# Power_Circuit.net
KiCad netlist of a schematic drawn in Altium Designer
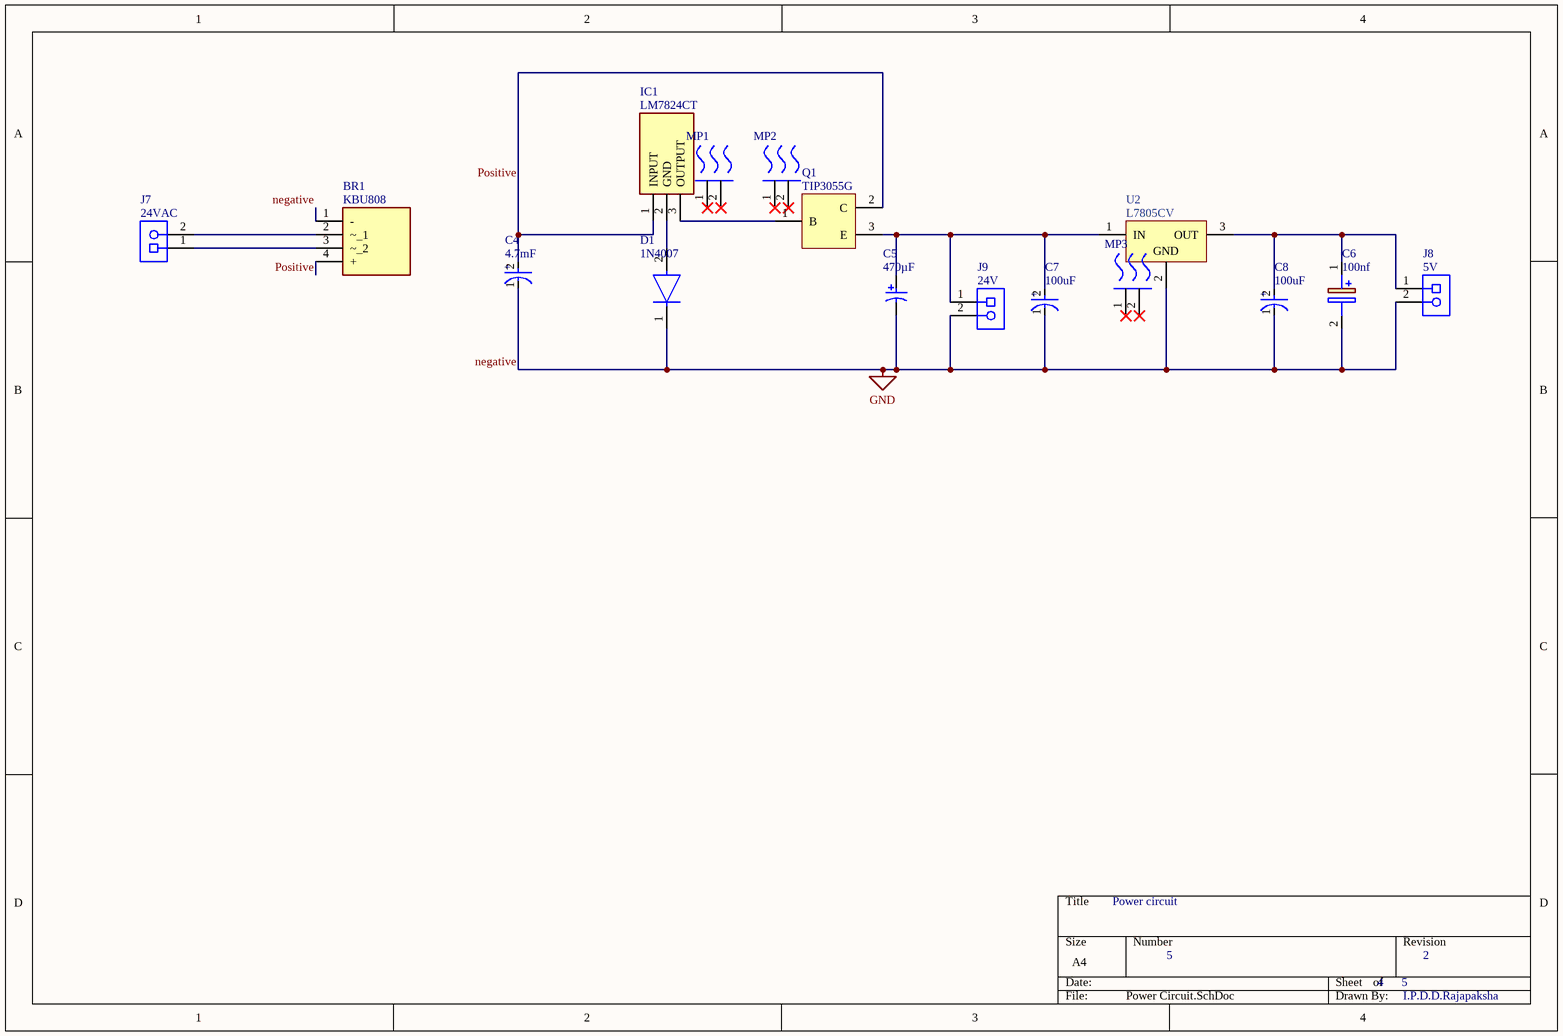
[diagram p0: Power Circuit.SchDoc]

(export (version "E")
  (design (tool "Eeschema 10.0.6"))
  (components
    (comp (ref "BR1")
      (value "KBU808")
      (footprint "SamacSys:KBU808")
      (description "Bridge Rectifier")
      (libsource (lib "SamacSys") (part "KBU808"))
    )
    (comp (ref "C4")
      (value "ECA1VHG472")
      (footprint "FP-RAD-TH-D_18_0_5-L_35_5-MFG")
      (description "Aluminum Electrolytic Capacitors (Radial Lead Type) AEC-Q200 Qualified 4700uF ±20% 35V")
      (fields
        (field (name "CAPACITANCE") "4.7mF")
        (field (name "VOLTAGE") "35V")
        (field (name "TOLERANCE") "20%")
      )
      (libsource (lib "Altium Content Vault") (part "203bc49f2ac43e59fd269a8c329ed05"))
    )
    (comp (ref "C5")
      (value "ECA-1HHG471")
      (footprint "PNSC-CAP-10x20-P2")
      (description "Aluminum Electrolytic Capacitor, 470 uF, +/- 20%, 50 V, -55 to 105 degC, 2-Pin THD, RoHS, Bulk")
      (fields (field (name "MANUFACTURER") "Panasonic") (field (name "CAPACITANCE") "470µF"))
      (libsource (lib "Altium Content Vault") (part "CAP-P-2"))
    )
    (comp (ref "C6")
      (value "ECEA1HKS0R1")
      (footprint "SamacSys:CAPPRD150W50D400H600")
      (description "Capacitor Polarised")
      (fields (field (name "PARAMETER 1") "100nf"))
      (libsource (lib "*") (part "ECEA1HKS0R1"))
    )
    (comp (ref "C7")
      (value "EEU-FR1H101B")
      (footprint "FP-EEU-FR1H101B-MFG")
      (description "CAP ALUM 100UF 20% 50V RADIAL")
      (fields (field (name "TOLERANCE") "20%") (field (name "CAPACITANCE") "100uF"))
      (libsource (lib "Altium Content Vault") (part "cf48714ba7e38822c1575c7ec0b6d1f"))
    )
    (comp (ref "C8")
      (value "EEU-FR1H101B")
      (footprint "FP-EEU-FR1H101B-MFG")
      (description "CAP ALUM 100UF 20% 50V RADIAL")
      (fields (field (name "TOLERANCE") "20%") (field (name "CAPACITANCE") "100uF"))
      (libsource (lib "Altium Content Vault") (part "cf48714ba7e38822c1575c7ec0b6d1f"))
    )
    (comp (ref "D1")
      (value "1N4007")
      (footprint "FP-1N4007-MFG")
      (description "Rectifier diode 1000 V 1 A DO-41, ,")
      (fields
        (field (name "MANUFACTURER") "Diotec")
        (field (name "OCTOPART") "https://octopart.com/1n4007-diotec-4040411")
      )
      (libsource (lib "Altium Content Vault") (part "d7152d700b627762746794eb795d46e"))
    )
    (comp (ref "IC1")
      (value "LM7824CT")
      (footprint "SamacSys:TO254P470X1028X1955-3P")
      (description "Integrated Circuit")
      (libsource (lib "*") (part "LM7824CT"))
    )
    (comp (ref "J7")
      (value "1729128")
      (footprint "PHOE-1729128-2_V")
      (description "PCB Terminal Block, 13.5 A, 400 V, 2-Pin THD, RoHS, Bulk")
      (fields (field (name "MANUFACTURER") "Phoenix Contact") (field (name "PARAMETER 1") "24VAC"))
      (libsource (lib "") (part "CN-2P-F-R2_1"))
    )
    (comp (ref "J8")
      (value "1729128")
      (footprint "PHOE-1729128-2_V")
      (description "PCB Terminal Block, 13.5 A, 400 V, 2-Pin THD, RoHS, Bulk")
      (fields (field (name "MANUFACTURER") "Phoenix Contact") (field (name "PARAMETER 1") "5V"))
      (libsource (lib "Altium Content Vault") (part "CN-2P-F-R2"))
    )
    (comp (ref "J9")
      (value "1729128")
      (footprint "PHOE-1729128-2_V")
      (description "PCB Terminal Block, 13.5 A, 400 V, 2-Pin THD, RoHS, Bulk")
      (fields (field (name "MANUFACTURER") "Phoenix Contact") (field (name "PARAMETER 1") "24V"))
      (libsource (lib "Altium Content Vault") (part "CN-2P-F-R2"))
    )
    (comp (ref "MP1")
      (value "WV-T264-101E")
      (footprint "FP-WV-T264-101E-MFG")
      (description "HEATSINK W/CLIP FOR TO-264")
      (libsource (lib "Altium Content Vault") (part "df9a98908f0b1072c7a35a179da30c1"))
    )
    (comp (ref "MP2")
      (value "WV-T264-101E")
      (footprint "FP-WV-T264-101E-MFG")
      (description "HEATSINK W/CLIP FOR TO-264")
      (libsource (lib "Altium Content Vault") (part "df9a98908f0b1072c7a35a179da30c1"))
    )
    (comp (ref "MP3")
      (value "WV-T264-101E")
      (footprint "FP-WV-T264-101E-MFG")
      (description "HEATSINK W/CLIP FOR TO-264")
      (libsource (lib "Altium Content Vault") (part "df9a98908f0b1072c7a35a179da30c1"))
    )
    (comp (ref "Q1")
      (value "TIP3055G")
      (footprint "ONSC-TO-247-3-340L-02")
      (description "Complementary Silicon Power Transistor, 3-Pin TO-247, Pb-Free, Tube")
      (fields (field (name "MANUFACTURER") "On Semiconductor"))
      (libsource (lib "Altium Content Vault") (part "ONSC-NPN-B1C2E3-3_B"))
    )
    (comp (ref "U2")
      (value "L7805CV")
      (footprint "TO220")
      (description "Positive Voltage Regulator, 5V, 3-Pin TO-220")
      (libsource (lib "Altium Content Vault") (part "PM-REG-L4940-SIL3"))
    )
  )
  (nets
    (net (code "1") (name "/Positive") (class "Default")
      (node (ref "BR1") (pin "4") (pinfunction "+_4") (pintype "passive"))
      (node (ref "C4") (pin "2") (pinfunction "A_2") (pintype "passive"))
      (node (ref "IC1") (pin "1") (pinfunction "INPUT_1") (pintype "passive"))
      (node (ref "Q1") (pin "2") (pinfunction "C_2") (pintype "passive"))
    )
    (net (code "2") (name "GND") (class "Default")
      (node (ref "BR1") (pin "1") (pinfunction "-_1") (pintype "passive"))
      (node (ref "C4") (pin "1") (pinfunction "C_1") (pintype "passive"))
      (node (ref "C5") (pin "2") (pinfunction "2_2") (pintype "passive"))
      (node (ref "C6") (pin "2") (pinfunction "-_2") (pintype "passive"))
      (node (ref "C7") (pin "1") (pinfunction "C_1") (pintype "passive"))
      (node (ref "C8") (pin "1") (pinfunction "C_1") (pintype "passive"))
      (node (ref "D1") (pin "1") (pinfunction "C_1") (pintype "passive"))
      (node (ref "J8") (pin "2") (pinfunction "2_2") (pintype "passive"))
      (node (ref "J9") (pin "2") (pinfunction "2_2") (pintype "passive"))
      (node (ref "U2") (pin "2") (pinfunction "GND_2") (pintype "power_in"))
    )
    (net (code "3") (name "Net-(BR1-~_1)") (class "Default")
      (node (ref "BR1") (pin "2") (pinfunction "~_1_2") (pintype "passive"))
      (node (ref "J7") (pin "2") (pinfunction "2_2") (pintype "passive"))
    )
    (net (code "4") (name "Net-(BR1-~_2)") (class "Default")
      (node (ref "BR1") (pin "3") (pinfunction "~_2_3") (pintype "passive"))
      (node (ref "J7") (pin "1") (pinfunction "1_1") (pintype "passive"))
    )
    (net (code "5") (name "Net-(C6-+)") (class "Default")
      (node (ref "C6") (pin "1") (pinfunction "+_1") (pintype "passive"))
      (node (ref "C8") (pin "2") (pinfunction "A_2") (pintype "passive"))
      (node (ref "J8") (pin "1") (pinfunction "1_1") (pintype "passive"))
      (node (ref "U2") (pin "3") (pinfunction "OUT_3") (pintype "power_in"))
    )
    (net (code "6") (name "Net-(C7-A)") (class "Default")
      (node (ref "C5") (pin "1") (pinfunction "1_1") (pintype "passive"))
      (node (ref "C7") (pin "2") (pinfunction "A_2") (pintype "passive"))
      (node (ref "J9") (pin "1") (pinfunction "1_1") (pintype "passive"))
      (node (ref "Q1") (pin "3") (pinfunction "E_3") (pintype "passive"))
      (node (ref "U2") (pin "1") (pinfunction "IN_1") (pintype "power_in"))
    )
    (net (code "7") (name "Net-(D1-A)") (class "Default")
      (node (ref "D1") (pin "2") (pinfunction "A_2") (pintype "passive"))
      (node (ref "IC1") (pin "2") (pinfunction "GND_2") (pintype "passive"))
    )
    (net (code "8") (name "Net-(IC1-OUTPUT)") (class "Default")
      (node (ref "IC1") (pin "3") (pinfunction "OUTPUT_3") (pintype "passive"))
      (node (ref "Q1") (pin "1") (pinfunction "B_1") (pintype "passive"))
    )
    (net (code "9") (name "unconnected-(MP1-MNT_1-Pad1)") (class "Default")
      (node (ref "MP1") (pin "1") (pinfunction "MNT_1_1") (pintype "passive+no_connect"))
    )
    (net (code "10") (name "unconnected-(MP1-MNT_2-Pad2)") (class "Default")
      (node (ref "MP1") (pin "2") (pinfunction "MNT_2_2") (pintype "passive+no_connect"))
    )
    (net (code "11") (name "unconnected-(MP2-MNT_1-Pad1)") (class "Default")
      (node (ref "MP2") (pin "1") (pinfunction "MNT_1_1") (pintype "passive+no_connect"))
    )
    (net (code "12") (name "unconnected-(MP2-MNT_2-Pad2)") (class "Default")
      (node (ref "MP2") (pin "2") (pinfunction "MNT_2_2") (pintype "passive+no_connect"))
    )
    (net (code "13") (name "unconnected-(MP3-MNT_1-Pad1)") (class "Default")
      (node (ref "MP3") (pin "1") (pinfunction "MNT_1_1") (pintype "passive+no_connect"))
    )
    (net (code "14") (name "unconnected-(MP3-MNT_2-Pad2)") (class "Default")
      (node (ref "MP3") (pin "2") (pinfunction "MNT_2_2") (pintype "passive+no_connect"))
    )
  )
)
